# openSX70-dongle-USB-V1.net
KiCad netlist of a schematic drawn in EAGLE
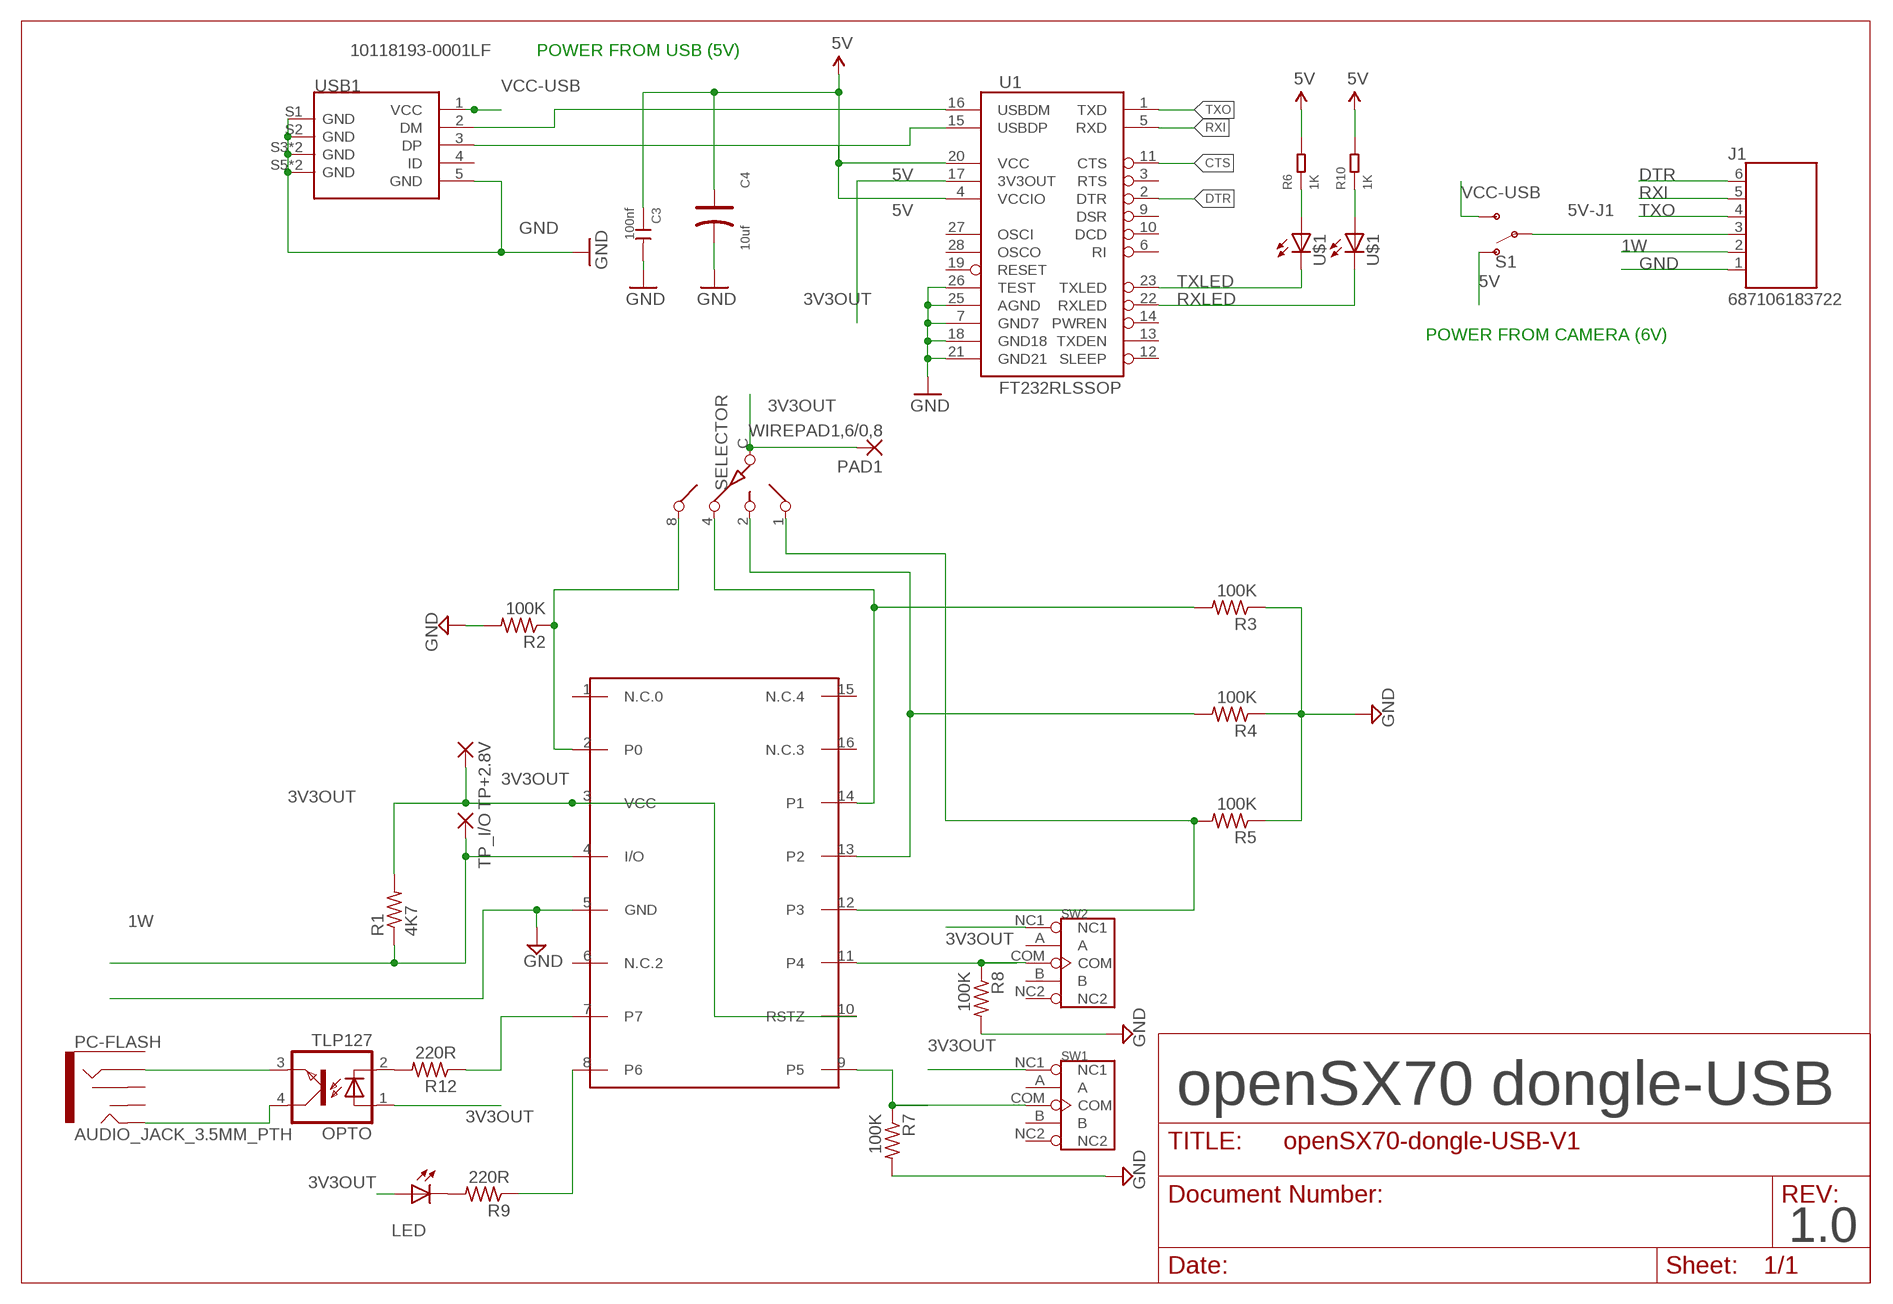
[diagram p0: schematic, sheet 1]

(export (version "E")
  (design (tool "Eeschema 10.0.6"))
  (components
    (comp (ref "C3")
      (value "100nf")
      (footprint "eagle-import:C0603")
      (fields (field (name "MPN") "CC0603KRX7R9BB104"))
      (libsource (lib "eagle-import") (part "CERAMIC-100NF-50V-10%-X7R(0603)"))
    )
    (comp (ref "C4")
      (value "10uf")
      (footprint "eagle-import:AVX-A")
      (fields (field (name "MPN") "TAJA106K016RNJ"))
      (libsource (lib "eagle-import") (part "TANTALUM-SMD-10UF-16V-10%(AVX-A)"))
    )
    (comp (ref "DS2408")
      (value "DS2408")
      (footprint "eagle-import:SO16")
      (libsource (lib "eagle-import") (part "DS2408"))
    )
    (comp (ref "J1")
      (value "687106183722")
      (footprint "eagle-import:687106183722")
      (fields (field (name "MF") "Wurth Electronics"))
      (libsource (lib "eagle-import") (part "687106183722"))
    )
    (comp (ref "LED")
      (value "LED3MM")
      (footprint "eagle-import:LED3MM")
      (libsource (lib "eagle-import") (part "LED3MM"))
    )
    (comp (ref "OPTO")
      (value "TLP127")
      (footprint "eagle-import:SO-4")
      (libsource (lib "eagle-import") (part "TLP127"))
    )
    (comp (ref "PAD1")
      (value "WIREPAD1,6/0,8")
      (footprint "eagle-import:1,6_0,8")
      (libsource (lib "eagle-import") (part "WIREPAD1,6/0,8"))
    )
    (comp (ref "PC-FLASH")
      (value "AUDIO_JACK_3.5MM_PTH")
      (footprint "eagle-import:AUDIO-JACK")
      (libsource (lib "eagle-import") (part "AUDIO_JACK_3.5MM_PTH"))
    )
    (comp (ref "R1")
      (value "4K7")
      (footprint "eagle-import:M0805")
      (libsource (lib "eagle-import") (part "R-US_M0805"))
    )
    (comp (ref "R2")
      (value "100K")
      (footprint "eagle-import:M0805")
      (libsource (lib "eagle-import") (part "R-US_M0805"))
    )
    (comp (ref "R3")
      (value "100K")
      (footprint "eagle-import:M0805")
      (libsource (lib "eagle-import") (part "R-US_M0805"))
    )
    (comp (ref "R4")
      (value "100K")
      (footprint "eagle-import:M0805")
      (libsource (lib "eagle-import") (part "R-US_M0805"))
    )
    (comp (ref "R5")
      (value "100K")
      (footprint "eagle-import:M0805")
      (libsource (lib "eagle-import") (part "R-US_M0805"))
    )
    (comp (ref "R6")
      (value "1K")
      (footprint "eagle-import:R0603")
      (fields (field (name "MPN") "RC0603FR-071KL"))
      (libsource (lib "eagle-import") (part "SMD-RES-1K-1%-1/10W(0603)"))
    )
    (comp (ref "R7")
      (value "100K")
      (footprint "eagle-import:M0805")
      (libsource (lib "eagle-import") (part "R-US_M0805"))
    )
    (comp (ref "R8")
      (value "100K")
      (footprint "eagle-import:M0805")
      (libsource (lib "eagle-import") (part "R-US_M0805"))
    )
    (comp (ref "R9")
      (value "220R")
      (footprint "eagle-import:M0805")
      (libsource (lib "eagle-import") (part "R-US_M0805"))
    )
    (comp (ref "R10")
      (value "1K")
      (footprint "eagle-import:R0603")
      (fields (field (name "MPN") "RC0603FR-071KL"))
      (libsource (lib "eagle-import") (part "SMD-RES-1K-1%-1/10W(0603)"))
    )
    (comp (ref "R12")
      (value "220R")
      (footprint "eagle-import:M0805")
      (libsource (lib "eagle-import") (part "R-US_M0805"))
    )
    (comp (ref "S1")
      (value "SWITCH-SPDT-SMD-RIGHT-ANGLE")
      (footprint "eagle-import:SWITCH_SPST_SMD_A")
      (libsource (lib "eagle-import") (part "SWITCH-SPDT-SMD-RIGHT-ANGLE"))
    )
    (comp (ref "SELECTOR")
      (value "SW-C16")
      (footprint "eagle-import:SW-C16")
      (libsource (lib "eagle-import") (part "SW-C16"))
    )
    (comp (ref "SW1")
      (value "DIP-TOGGLE-SWITCH-ON-ON(3+2P-8.8X4.6MM)-90D")
      (footprint "eagle-import:SW5-2.0-8.8X4.4X4.7MM-90D")
      (fields (field (name "MPN") "3P-2.0-90D3P-2.0-90D-REINFORCE"))
      (libsource (lib "eagle-import") (part "DIP-TOGGLE-SWITCH-ON-ON(3+2P-8.8X4.6MM)-90D"))
    )
    (comp (ref "SW2")
      (value "DIP-TOGGLE-SWITCH-ON-ON(3+2P-8.8X4.6MM)-90D")
      (footprint "eagle-import:SW5-2.0-8.8X4.4X4.7MM-90D")
      (fields (field (name "MPN") "3P-2.0-90D3P-2.0-90D-REINFORCE"))
      (libsource (lib "eagle-import") (part "DIP-TOGGLE-SWITCH-ON-ON(3+2P-8.8X4.6MM)-90D"))
    )
    (comp (ref "TP+2.8V")
      (value "SMD2")
      (footprint "eagle-import:SMD1,27-2,54")
      (libsource (lib "eagle-import") (part "SMD2"))
    )
    (comp (ref "TP_I/O")
      (value "SMD2")
      (footprint "eagle-import:SMD1,27-2,54")
      (libsource (lib "eagle-import") (part "SMD2"))
    )
    (comp (ref "U$1")
      (value "DUAL-LED-0603-BIS")
      (footprint "eagle-import:LED_APHB1608SYKSURKC")
      (libsource (lib "eagle-import") (part "DUAL-LED-0603-BIS"))
    )
    (comp (ref "U1")
      (value "FT232RLSSOP")
      (footprint "eagle-import:SSOP28DB")
      (libsource (lib "eagle-import") (part "FT232RLSSOP"))
    )
    (comp (ref "USB1")
      (value "10118193-0001LF")
      (footprint "eagle-import:MICRO-USB5+6P-SMD-0.65-B")
      (libsource (lib "eagle-import") (part "MICRO-USB-SMD-B-(10118193-0001LF)"))
    )
  )
  (nets
    (net (code "1") (name "/1W") (class "Default")
      (node (ref "DS2408") (pin "4") (pinfunction "I/O_4") (pintype "bidirectional"))
      (node (ref "J1") (pin "2") (pinfunction "5_2") (pintype "passive"))
      (node (ref "R1") (pin "1") (pinfunction "1_1") (pintype "passive"))
      (node (ref "TP_I/O") (pin "1") (pinfunction "P_1") (pintype "passive"))
    )
    (net (code "2") (name "/3V3OUT") (class "Default")
      (node (ref "DS2408") (pin "10") (pinfunction "RSTZ_10") (pintype "bidirectional"))
      (node (ref "DS2408") (pin "3") (pinfunction "VCC_3") (pintype "bidirectional"))
      (node (ref "LED") (pin "A") (pinfunction "A_A") (pintype "passive"))
      (node (ref "OPTO") (pin "1") (pinfunction "A_1") (pintype "passive"))
      (node (ref "PAD1") (pin "1") (pinfunction "P_1") (pintype "passive"))
      (node (ref "R1") (pin "2") (pinfunction "2_2") (pintype "passive"))
      (node (ref "SELECTOR") (pin "C") (pinfunction "C_C") (pintype "passive"))
      (node (ref "SW1") (pin "NC1") (pinfunction "NC1_NC1") (pintype "bidirectional"))
      (node (ref "SW2") (pin "NC1") (pinfunction "NC1_NC1") (pintype "bidirectional"))
      (node (ref "TP+2.8V") (pin "1") (pinfunction "P_1") (pintype "passive"))
      (node (ref "U1") (pin "17") (pinfunction "3V3OUT_17") (pintype "output"))
    )
    (net (code "3") (name "/5V-J1") (class "Default")
      (node (ref "J1") (pin "3") (pinfunction "4_3") (pintype "passive"))
      (node (ref "S1") (pin "2") (pinfunction "P_2") (pintype "passive"))
    )
    (net (code "4") (name "/RXLED") (class "Default")
      (node (ref "U$1") (pin "4") (pinfunction "C1_4") (pintype "passive"))
      (node (ref "U1") (pin "22") (pinfunction "RXLED_22") (pintype "input"))
    )
    (net (code "5") (name "/TXLED") (class "Default")
      (node (ref "U$1") (pin "2") (pinfunction "C_2") (pintype "passive"))
      (node (ref "U1") (pin "23") (pinfunction "TXLED_23") (pintype "input"))
    )
    (net (code "6") (name "/VCC-USB") (class "Default")
      (node (ref "S1") (pin "3") (pinfunction "S_3") (pintype "passive"))
      (node (ref "USB1") (pin "1") (pinfunction "VCC_1") (pintype "bidirectional"))
    )
    (net (code "7") (name "5V") (class "Default")
      (node (ref "C3") (pin "1") (pinfunction "1_1") (pintype "passive"))
      (node (ref "C4") (pin "+") (pinfunction "+_+") (pintype "passive"))
      (node (ref "R10") (pin "2") (pinfunction "2_2") (pintype "passive"))
      (node (ref "R6") (pin "2") (pinfunction "2_2") (pintype "passive"))
      (node (ref "S1") (pin "1") (pinfunction "O_1") (pintype "passive"))
      (node (ref "U1") (pin "20") (pinfunction "VCC_20") (pintype "power_in"))
      (node (ref "U1") (pin "4") (pinfunction "VCCIO_4") (pintype "power_in"))
    )
    (net (code "8") (name "CTS") (class "Default")
      (node (ref "U1") (pin "11") (pinfunction "CTS_11") (pintype "input"))
    )
    (net (code "9") (name "DTR") (class "Default")
      (node (ref "J1") (pin "6") (pinfunction "1_6") (pintype "passive"))
      (node (ref "U1") (pin "2") (pinfunction "DTR_2") (pintype "output"))
    )
    (net (code "10") (name "GND") (class "Default")
      (node (ref "C3") (pin "2") (pinfunction "2_2") (pintype "passive"))
      (node (ref "C4") (pin "-") (pinfunction "-_-") (pintype "passive"))
      (node (ref "DS2408") (pin "5") (pinfunction "GND_5") (pintype "bidirectional"))
      (node (ref "J1") (pin "1") (pinfunction "6_1") (pintype "passive"))
      (node (ref "R2") (pin "2") (pinfunction "2_2") (pintype "passive"))
      (node (ref "R3") (pin "1") (pinfunction "1_1") (pintype "passive"))
      (node (ref "R4") (pin "1") (pinfunction "1_1") (pintype "passive"))
      (node (ref "R5") (pin "1") (pinfunction "1_1") (pintype "passive"))
      (node (ref "R7") (pin "2") (pinfunction "2_2") (pintype "passive"))
      (node (ref "R8") (pin "2") (pinfunction "2_2") (pintype "passive"))
      (node (ref "U1") (pin "18") (pinfunction "GND18_18") (pintype "power_in"))
      (node (ref "U1") (pin "21") (pinfunction "GND21_21") (pintype "power_in"))
      (node (ref "U1") (pin "25") (pinfunction "AGND_25") (pintype "power_in"))
      (node (ref "U1") (pin "26") (pinfunction "TEST_26") (pintype "input"))
      (node (ref "U1") (pin "7") (pinfunction "GND7_7") (pintype "power_in"))
      (node (ref "USB1") (pin "5") (pinfunction "GND_5") (pintype "bidirectional"))
      (node (ref "USB1") (pin "S1") (pinfunction "GND_S1") (pintype "bidirectional"))
      (node (ref "USB1") (pin "S2") (pinfunction "GND_S2") (pintype "bidirectional"))
      (node (ref "USB1") (pin "S3") (pinfunction "GND_S3") (pintype "bidirectional"))
      (node (ref "USB1") (pin "S4") (pinfunction "GND_S4") (pintype "bidirectional"))
      (node (ref "USB1") (pin "S5") (pinfunction "GND_S5") (pintype "bidirectional"))
      (node (ref "USB1") (pin "S6") (pinfunction "GND_S6") (pintype "bidirectional"))
    )
    (net (code "11") (name "Net-(DS2408-P0)") (class "Default")
      (node (ref "DS2408") (pin "2") (pinfunction "P0_2") (pintype "bidirectional"))
      (node (ref "R2") (pin "1") (pinfunction "1_1") (pintype "passive"))
      (node (ref "SELECTOR") (pin "8") (pinfunction "8_8") (pintype "passive"))
    )
    (net (code "12") (name "Net-(DS2408-P1)") (class "Default")
      (node (ref "DS2408") (pin "14") (pinfunction "P1_14") (pintype "bidirectional"))
      (node (ref "R3") (pin "2") (pinfunction "2_2") (pintype "passive"))
      (node (ref "SELECTOR") (pin "4") (pinfunction "4_4") (pintype "passive"))
    )
    (net (code "13") (name "Net-(DS2408-P2)") (class "Default")
      (node (ref "DS2408") (pin "13") (pinfunction "P2_13") (pintype "bidirectional"))
      (node (ref "R4") (pin "2") (pinfunction "2_2") (pintype "passive"))
      (node (ref "SELECTOR") (pin "2") (pinfunction "2_2") (pintype "passive"))
    )
    (net (code "14") (name "Net-(DS2408-P3)") (class "Default")
      (node (ref "DS2408") (pin "12") (pinfunction "P3_12") (pintype "bidirectional"))
      (node (ref "R5") (pin "2") (pinfunction "2_2") (pintype "passive"))
      (node (ref "SELECTOR") (pin "1") (pinfunction "1_1") (pintype "passive"))
    )
    (net (code "15") (name "Net-(DS2408-P4)") (class "Default")
      (node (ref "DS2408") (pin "11") (pinfunction "P4_11") (pintype "bidirectional"))
      (node (ref "R8") (pin "1") (pinfunction "1_1") (pintype "passive"))
      (node (ref "SW2") (pin "COM") (pinfunction "COM_COM") (pintype "bidirectional"))
    )
    (net (code "16") (name "Net-(DS2408-P5)") (class "Default")
      (node (ref "DS2408") (pin "9") (pinfunction "P5_9") (pintype "bidirectional"))
      (node (ref "R7") (pin "1") (pinfunction "1_1") (pintype "passive"))
      (node (ref "SW1") (pin "COM") (pinfunction "COM_COM") (pintype "bidirectional"))
    )
    (net (code "17") (name "Net-(DS2408-P6)") (class "Default")
      (node (ref "DS2408") (pin "8") (pinfunction "P6_8") (pintype "bidirectional"))
      (node (ref "R9") (pin "1") (pinfunction "1_1") (pintype "passive"))
    )
    (net (code "18") (name "Net-(DS2408-P7)") (class "Default")
      (node (ref "DS2408") (pin "7") (pinfunction "P7_7") (pintype "bidirectional"))
      (node (ref "R12") (pin "1") (pinfunction "1_1") (pintype "passive"))
    )
    (net (code "19") (name "Net-(LED-C)") (class "Default")
      (node (ref "LED") (pin "K") (pinfunction "C_K") (pintype "passive"))
      (node (ref "R9") (pin "2") (pinfunction "2_2") (pintype "passive"))
    )
    (net (code "20") (name "Net-(OPTO-C)") (class "Default")
      (node (ref "OPTO") (pin "2") (pinfunction "C_2") (pintype "passive"))
      (node (ref "R12") (pin "2") (pinfunction "2_2") (pintype "passive"))
    )
    (net (code "21") (name "Net-(OPTO-COL)") (class "Default")
      (node (ref "OPTO") (pin "4") (pinfunction "COL_4") (pintype "passive"))
      (node (ref "PC-FLASH") (pin "TIP") (pinfunction "TIP_TIP") (pintype "bidirectional"))
    )
    (net (code "22") (name "Net-(OPTO-EMIT)") (class "Default")
      (node (ref "OPTO") (pin "3") (pinfunction "EMIT_3") (pintype "passive"))
      (node (ref "PC-FLASH") (pin "RING") (pinfunction "RING_RING") (pintype "bidirectional"))
    )
    (net (code "23") (name "Net-(U$1-A)") (class "Default")
      (node (ref "R6") (pin "1") (pinfunction "1_1") (pintype "passive"))
      (node (ref "U$1") (pin "1") (pinfunction "A_1") (pintype "passive"))
    )
    (net (code "24") (name "Net-(U$1-A1)") (class "Default")
      (node (ref "R10") (pin "1") (pinfunction "1_1") (pintype "passive"))
      (node (ref "U$1") (pin "3") (pinfunction "A1_3") (pintype "passive"))
    )
    (net (code "25") (name "Net-(U1-USBDM)") (class "Default")
      (node (ref "U1") (pin "16") (pinfunction "USBDM_16") (pintype "bidirectional"))
      (node (ref "USB1") (pin "2") (pinfunction "DM_2") (pintype "bidirectional"))
    )
    (net (code "26") (name "Net-(U1-USBDP)") (class "Default")
      (node (ref "U1") (pin "15") (pinfunction "USBDP_15") (pintype "bidirectional"))
      (node (ref "USB1") (pin "3") (pinfunction "DP_3") (pintype "bidirectional"))
    )
    (net (code "27") (name "RXI") (class "Default")
      (node (ref "J1") (pin "5") (pinfunction "2_5") (pintype "passive"))
      (node (ref "U1") (pin "5") (pinfunction "RXD_5") (pintype "input"))
    )
    (net (code "28") (name "TXO") (class "Default")
      (node (ref "J1") (pin "4") (pinfunction "3_4") (pintype "passive"))
      (node (ref "U1") (pin "1") (pinfunction "TXD_1") (pintype "output"))
    )
    (net (code "29") (name "unconnected-(DS2408-N.C.0-Pad1)") (class "Default")
      (node (ref "DS2408") (pin "1") (pinfunction "N.C.0_1") (pintype "bidirectional"))
    )
    (net (code "30") (name "unconnected-(DS2408-N.C.2-Pad6)") (class "Default")
      (node (ref "DS2408") (pin "6") (pinfunction "N.C.2_6") (pintype "bidirectional"))
    )
    (net (code "31") (name "unconnected-(DS2408-N.C.3-Pad16)") (class "Default")
      (node (ref "DS2408") (pin "16") (pinfunction "N.C.3_16") (pintype "bidirectional"))
    )
    (net (code "32") (name "unconnected-(DS2408-N.C.4-Pad15)") (class "Default")
      (node (ref "DS2408") (pin "15") (pinfunction "N.C.4_15") (pintype "bidirectional"))
    )
    (net (code "33") (name "unconnected-(PC-FLASH-PadRSH)") (class "Default")
      (node (ref "PC-FLASH") (pin "RSH") (pinfunction "RSH_RSH") (pintype "bidirectional"))
    )
    (net (code "34") (name "unconnected-(PC-FLASH-PadSLEEVE)") (class "Default")
      (node (ref "PC-FLASH") (pin "SLEEVE") (pinfunction "SLEEVE_SLEEVE") (pintype "bidirectional"))
    )
    (net (code "35") (name "unconnected-(PC-FLASH-PadTSH)") (class "Default")
      (node (ref "PC-FLASH") (pin "TSH") (pinfunction "TSH_TSH") (pintype "bidirectional"))
    )
    (net (code "36") (name "unconnected-(SW1-PadA)") (class "Default")
      (node (ref "SW1") (pin "A") (pinfunction "A_A") (pintype "bidirectional"))
    )
    (net (code "37") (name "unconnected-(SW1-PadB)") (class "Default")
      (node (ref "SW1") (pin "B") (pinfunction "B_B") (pintype "bidirectional"))
    )
    (net (code "38") (name "unconnected-(SW1-PadNC2)") (class "Default")
      (node (ref "SW1") (pin "NC2") (pinfunction "NC2_NC2") (pintype "bidirectional"))
    )
    (net (code "39") (name "unconnected-(SW2-PadA)") (class "Default")
      (node (ref "SW2") (pin "A") (pinfunction "A_A") (pintype "bidirectional"))
    )
    (net (code "40") (name "unconnected-(SW2-PadB)") (class "Default")
      (node (ref "SW2") (pin "B") (pinfunction "B_B") (pintype "bidirectional"))
    )
    (net (code "41") (name "unconnected-(SW2-PadNC2)") (class "Default")
      (node (ref "SW2") (pin "NC2") (pinfunction "NC2_NC2") (pintype "bidirectional"))
    )
    (net (code "42") (name "unconnected-(U1-DCD-Pad10)") (class "Default")
      (node (ref "U1") (pin "10") (pinfunction "DCD_10") (pintype "input"))
    )
    (net (code "43") (name "unconnected-(U1-DSR-Pad9)") (class "Default")
      (node (ref "U1") (pin "9") (pinfunction "DSR_9") (pintype "input"))
    )
    (net (code "44") (name "unconnected-(U1-OSCI-Pad27)") (class "Default")
      (node (ref "U1") (pin "27") (pinfunction "OSCI_27") (pintype "input"))
    )
    (net (code "45") (name "unconnected-(U1-OSCO-Pad28)") (class "Default")
      (node (ref "U1") (pin "28") (pinfunction "OSCO_28") (pintype "output"))
    )
    (net (code "46") (name "unconnected-(U1-PWREN-Pad14)") (class "Default")
      (node (ref "U1") (pin "14") (pinfunction "PWREN_14") (pintype "input"))
    )
    (net (code "47") (name "unconnected-(U1-RESET-Pad19)") (class "Default")
      (node (ref "U1") (pin "19") (pinfunction "RESET_19") (pintype "input"))
    )
    (net (code "48") (name "unconnected-(U1-RI-Pad6)") (class "Default")
      (node (ref "U1") (pin "6") (pinfunction "RI_6") (pintype "input"))
    )
    (net (code "49") (name "unconnected-(U1-RTS-Pad3)") (class "Default")
      (node (ref "U1") (pin "3") (pinfunction "RTS_3") (pintype "output"))
    )
    (net (code "50") (name "unconnected-(U1-SLEEP-Pad12)") (class "Default")
      (node (ref "U1") (pin "12") (pinfunction "SLEEP_12") (pintype "input"))
    )
    (net (code "51") (name "unconnected-(U1-TXDEN-Pad13)") (class "Default")
      (node (ref "U1") (pin "13") (pinfunction "TXDEN_13") (pintype "input"))
    )
    (net (code "52") (name "unconnected-(USB1-ID-Pad4)") (class "Default")
      (node (ref "USB1") (pin "4") (pinfunction "ID_4") (pintype "bidirectional"))
    )
  )
)
